# Sheet3.net
KiCad netlist of a schematic drawn in Altium Designer
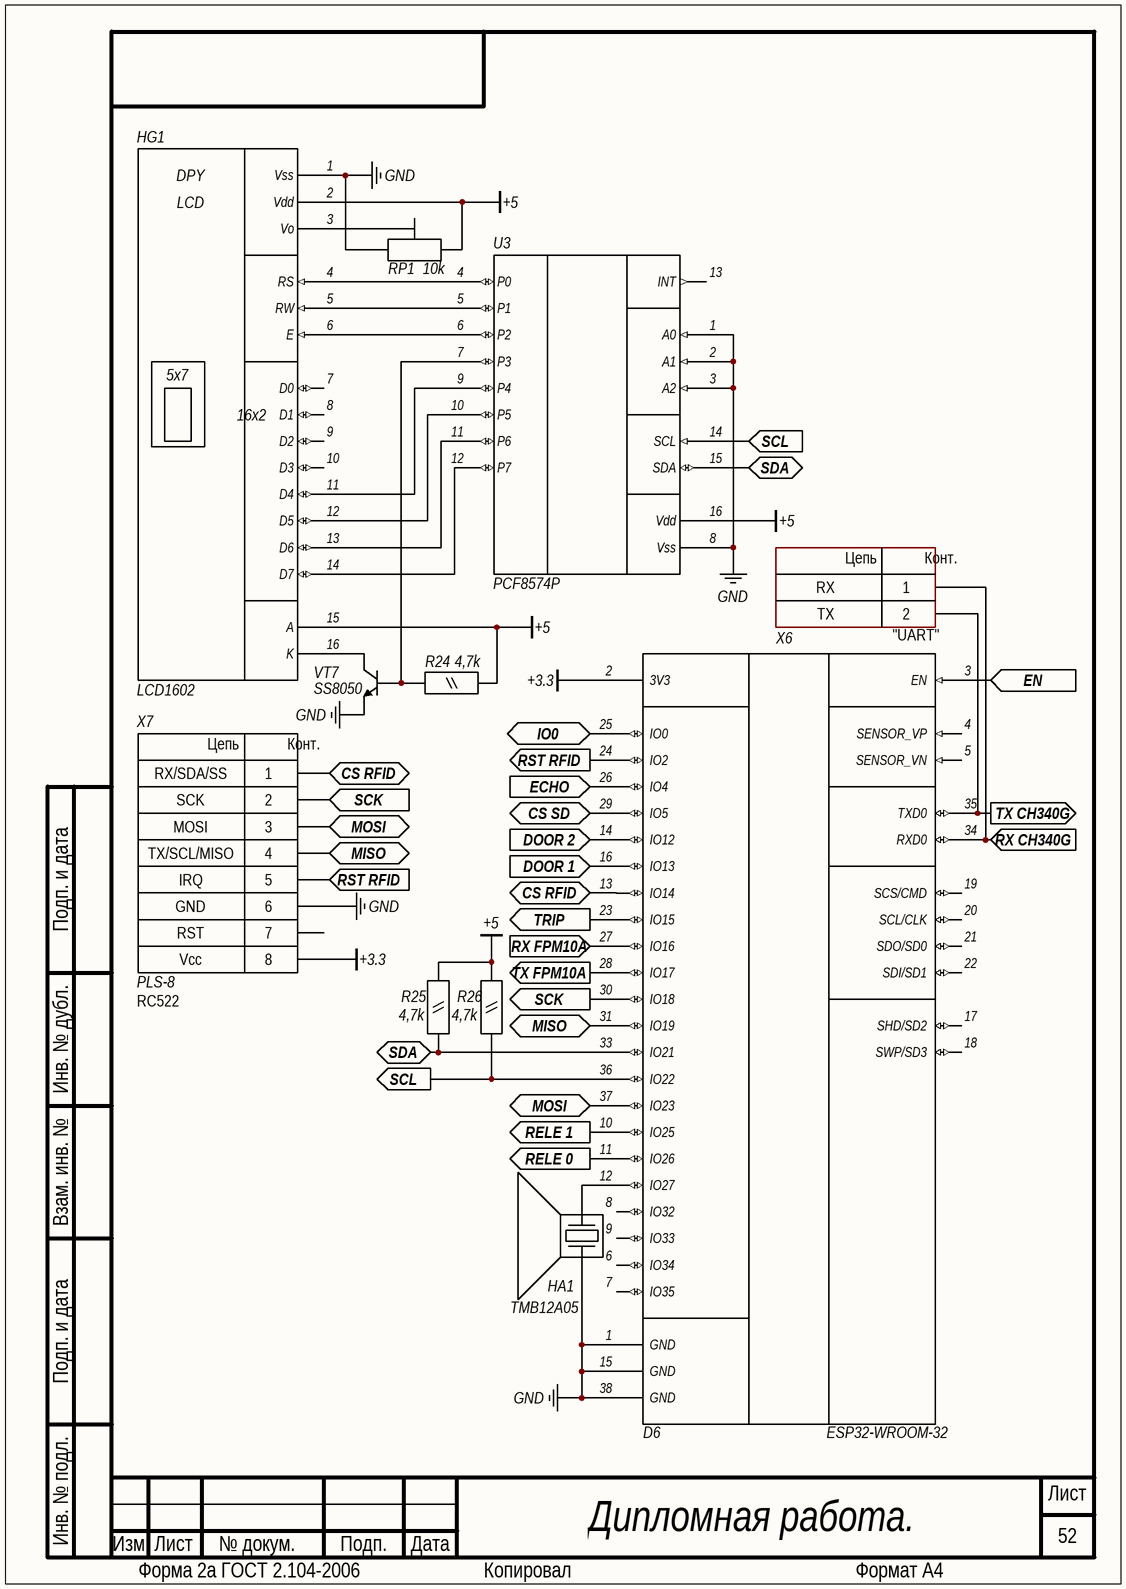
[diagram p0: Sheet3.SchDoc]

(export (version "E")
  (design (tool "Eeschema 10.0.6"))
  (components
    (comp (ref "D6")
      (value "ESP32-WROOM-32")
      (footprint "D ESP-WROOOM-32")
      (fields (field (name "MANUFACTURER") "Espressif Systems"))
      (libsource (lib "Schlib") (part "ESP32-WROOM"))
    )
    (comp (ref "HA1")
      (value "TMB12A05")
      (footprint "HA TMB12A05")
      (libsource (lib "Schlib") (part "Пьездодинамик"))
    )
    (comp (ref "HG1")
      (value "LCD1602")
      (footprint "X PBS-16")
      (description "Дисплей на основе контроллера HD44780.")
      (libsource (lib "Schlib") (part "LCD HD44780"))
    )
    (comp (ref "R24")
      (value "4,7k")
      (footprint "R SMD 0805")
      (description "R")
      (fields (field (name "POWER") "0.125"))
      (libsource (lib "") (part "Резистор 0.125 Вт_1"))
    )
    (comp (ref "R25")
      (value "4,7k")
      (footprint "R SMD 0805")
      (description "R")
      (fields (field (name "POWER") "0.125"))
      (libsource (lib "Schlib") (part "Резистор 0.125 Вт"))
    )
    (comp (ref "R26")
      (value "4,7k")
      (footprint "R SMD 0805")
      (description "R")
      (fields (field (name "POWER") "0.125"))
      (libsource (lib "Schlib") (part "Резистор 0.125 Вт"))
    )
    (comp (ref "RP1")
      (value "10k")
      (footprint "R ADJ-3296W")
      (libsource (lib "Schlib") (part "Подстроечный Резистор"))
    )
    (comp (ref "U3")
      (value "PCF8574P")
      (footprint "U DIP-16")
      (description "IIC расширитель.")
      (libsource (lib "Schlib") (part "PCF8574"))
    )
    (comp (ref "VT7")
      (value "SS8050")
      (footprint "U SOT-23-3")
      (fields (field (name "MANUFACTURER") "Hottech"))
      (libsource (lib "Schlib") (part "Биполярный Транзистор"))
    )
    (comp (ref "X6")
      (value "~")
      (footprint "CustomCase:CON: PLS-2")
      (fields
        (field (name "MANUFACTURER") "Connfly")
        (field (name "VALUEMANUFACTURERPARTNUMBER") "Connector, 2pin, 2.54mm, 500VAC, 3A")
        (field (name "PARTNUMBER") "PLS-2")
        (field (name "COMMENTTEXT") "\"UART\"")
        (field (name "TEXT1") "RX")
        (field (name "TEXT2") "TX")
      )
      (libsource (lib "Connector") (part "PLS-2"))
    )
    (comp (ref "X7")
      (value "PLS-8")
      (footprint "X PLS-8")
      (fields (field (name "COMMENTTEXT") "RC522"))
      (libsource (lib "Schlib") (part "PLS/PBS-8"))
    )
  )
  (nets
    (net (code "1") (name "+3.3") (class "Default")
      (node (ref "D6") (pin "2") (pinfunction "3V3_2") (pintype "power_in"))
      (node (ref "X7") (pin "8") (pinfunction "8_8") (pintype "power_in"))
    )
    (net (code "2") (name "+5") (class "Default")
      (node (ref "HG1") (pin "15") (pinfunction "A_15") (pintype "power_in"))
      (node (ref "HG1") (pin "2") (pinfunction "Vdd_2") (pintype "power_in"))
      (node (ref "R24") (pin "1") (pintype "passive"))
      (node (ref "R25") (pin "1") (pintype "passive"))
      (node (ref "R26") (pin "1") (pintype "passive"))
      (node (ref "RP1") (pin "1") (pintype "power_in"))
      (node (ref "U3") (pin "16") (pinfunction "Vdd_16") (pintype "power_in"))
    )
    (net (code "3") (name "/CS RFID") (class "Default")
      (node (ref "D6") (pin "13") (pinfunction "IO14_13") (pintype "bidirectional"))
      (node (ref "X7") (pin "1") (pinfunction "1_1") (pintype "passive"))
    )
    (net (code "4") (name "/CS SD") (class "Default")
      (node (ref "D6") (pin "29") (pinfunction "IO5_29") (pintype "bidirectional"))
    )
    (net (code "5") (name "/DOOR 1") (class "Default")
      (node (ref "D6") (pin "16") (pinfunction "IO13_16") (pintype "bidirectional"))
    )
    (net (code "6") (name "/DOOR 2") (class "Default")
      (node (ref "D6") (pin "14") (pinfunction "IO12_14") (pintype "bidirectional"))
    )
    (net (code "7") (name "/ECHO") (class "Default")
      (node (ref "D6") (pin "26") (pinfunction "IO4_26") (pintype "bidirectional"))
    )
    (net (code "8") (name "/EN") (class "Default")
      (node (ref "D6") (pin "3") (pinfunction "EN_3") (pintype "input"))
    )
    (net (code "9") (name "/IO0") (class "Default")
      (node (ref "D6") (pin "25") (pinfunction "IO0_25") (pintype "bidirectional"))
    )
    (net (code "10") (name "/MISO") (class "Default")
      (node (ref "D6") (pin "31") (pinfunction "IO19_31") (pintype "bidirectional"))
      (node (ref "X7") (pin "4") (pinfunction "4_4") (pintype "power_in"))
    )
    (net (code "11") (name "/MOSI") (class "Default")
      (node (ref "D6") (pin "37") (pinfunction "IO23_37") (pintype "bidirectional"))
      (node (ref "X7") (pin "3") (pinfunction "3_3") (pintype "power_in"))
    )
    (net (code "12") (name "/RELE 0") (class "Default")
      (node (ref "D6") (pin "11") (pinfunction "IO26_11") (pintype "bidirectional"))
    )
    (net (code "13") (name "/RELE 1") (class "Default")
      (node (ref "D6") (pin "10") (pinfunction "IO25_10") (pintype "bidirectional"))
    )
    (net (code "14") (name "/RST RFID") (class "Default")
      (node (ref "D6") (pin "24") (pinfunction "IO2_24") (pintype "bidirectional"))
      (node (ref "X7") (pin "5") (pinfunction "5_5") (pintype "power_in"))
    )
    (net (code "15") (name "/RX CH340G") (class "Default")
      (node (ref "D6") (pin "34") (pinfunction "RXD0_34") (pintype "bidirectional"))
      (node (ref "X6") (pin "1") (pinfunction "1_1") (pintype "passive"))
    )
    (net (code "16") (name "/RX FPM10A") (class "Default")
      (node (ref "D6") (pin "27") (pinfunction "IO16_27") (pintype "bidirectional"))
    )
    (net (code "17") (name "/SCK") (class "Default")
      (node (ref "D6") (pin "30") (pinfunction "IO18_30") (pintype "bidirectional"))
      (node (ref "X7") (pin "2") (pinfunction "2_2") (pintype "passive"))
    )
    (net (code "18") (name "/SCL") (class "Default")
      (node (ref "D6") (pin "36") (pinfunction "IO22_36") (pintype "bidirectional"))
      (node (ref "R26") (pin "2") (pintype "passive"))
      (node (ref "U3") (pin "14") (pinfunction "SCL_14") (pintype "input"))
    )
    (net (code "19") (name "/SDA") (class "Default")
      (node (ref "D6") (pin "33") (pinfunction "IO21_33") (pintype "bidirectional"))
      (node (ref "R25") (pin "2") (pintype "passive"))
      (node (ref "U3") (pin "15") (pinfunction "SDA_15") (pintype "bidirectional"))
    )
    (net (code "20") (name "/TRIP") (class "Default")
      (node (ref "D6") (pin "23") (pinfunction "IO15_23") (pintype "bidirectional"))
    )
    (net (code "21") (name "/TX CH340G") (class "Default")
      (node (ref "D6") (pin "35") (pinfunction "TXD0_35") (pintype "bidirectional"))
      (node (ref "X6") (pin "2") (pinfunction "2_2") (pintype "passive"))
    )
    (net (code "22") (name "/TX FPM10A") (class "Default")
      (node (ref "D6") (pin "28") (pinfunction "IO17_28") (pintype "bidirectional"))
    )
    (net (code "23") (name "GND") (class "Default")
      (node (ref "D6") (pin "1") (pinfunction "GND_1") (pintype "power_in"))
      (node (ref "D6") (pin "15") (pinfunction "GND_15") (pintype "power_in"))
      (node (ref "D6") (pin "38") (pinfunction "GND_38") (pintype "power_in"))
      (node (ref "HA1") (pin "2") (pinfunction "-_2") (pintype "passive"))
      (node (ref "HG1") (pin "1") (pinfunction "Vss_1") (pintype "power_in"))
      (node (ref "RP1") (pin "3") (pintype "power_in"))
      (node (ref "U3") (pin "1") (pinfunction "A0_1") (pintype "input"))
      (node (ref "U3") (pin "2") (pinfunction "A1_2") (pintype "input"))
      (node (ref "U3") (pin "3") (pinfunction "A2_3") (pintype "input"))
      (node (ref "U3") (pin "8") (pinfunction "Vss_8") (pintype "power_in"))
      (node (ref "VT7") (pin "1") (pinfunction "E_1") (pintype "open_emitter"))
      (node (ref "X7") (pin "6") (pinfunction "6_6") (pintype "power_in"))
    )
    (net (code "24") (name "Net-(D6-IO27)") (class "Default")
      (node (ref "D6") (pin "12") (pinfunction "IO27_12") (pintype "bidirectional"))
      (node (ref "HA1") (pin "1") (pinfunction "+_1") (pintype "passive"))
    )
    (net (code "25") (name "Net-(HG1-D4)") (class "Default")
      (node (ref "HG1") (pin "11") (pinfunction "D4_11") (pintype "bidirectional"))
      (node (ref "U3") (pin "9") (pinfunction "P4_9") (pintype "bidirectional"))
    )
    (net (code "26") (name "Net-(HG1-D5)") (class "Default")
      (node (ref "HG1") (pin "12") (pinfunction "D5_12") (pintype "bidirectional"))
      (node (ref "U3") (pin "10") (pinfunction "P5_10") (pintype "bidirectional"))
    )
    (net (code "27") (name "Net-(HG1-D6)") (class "Default")
      (node (ref "HG1") (pin "13") (pinfunction "D6_13") (pintype "bidirectional"))
      (node (ref "U3") (pin "11") (pinfunction "P6_11") (pintype "bidirectional"))
    )
    (net (code "28") (name "Net-(HG1-D7)") (class "Default")
      (node (ref "HG1") (pin "14") (pinfunction "D7_14") (pintype "bidirectional"))
      (node (ref "U3") (pin "12") (pinfunction "P7_12") (pintype "bidirectional"))
    )
    (net (code "29") (name "Net-(HG1-E)") (class "Default")
      (node (ref "HG1") (pin "6") (pinfunction "E_6") (pintype "input"))
      (node (ref "U3") (pin "6") (pinfunction "P2_6") (pintype "bidirectional"))
    )
    (net (code "30") (name "Net-(HG1-K)") (class "Default")
      (node (ref "HG1") (pin "16") (pinfunction "K_16") (pintype "power_in"))
      (node (ref "VT7") (pin "3") (pinfunction "C_3") (pintype "open_collector"))
    )
    (net (code "31") (name "Net-(HG1-RS)") (class "Default")
      (node (ref "HG1") (pin "4") (pinfunction "RS_4") (pintype "input"))
      (node (ref "U3") (pin "4") (pinfunction "P0_4") (pintype "bidirectional"))
    )
    (net (code "32") (name "Net-(HG1-RW)") (class "Default")
      (node (ref "HG1") (pin "5") (pinfunction "RW_5") (pintype "input"))
      (node (ref "U3") (pin "5") (pinfunction "P1_5") (pintype "bidirectional"))
    )
    (net (code "33") (name "Net-(HG1-Vo)") (class "Default")
      (node (ref "HG1") (pin "3") (pinfunction "Vo_3") (pintype "power_in"))
      (node (ref "RP1") (pin "2") (pintype "power_in"))
    )
    (net (code "34") (name "Net-(U3-P3)") (class "Default")
      (node (ref "R24") (pin "2") (pintype "passive"))
      (node (ref "U3") (pin "7") (pinfunction "P3_7") (pintype "bidirectional"))
      (node (ref "VT7") (pin "2") (pinfunction "B_2") (pintype "passive"))
    )
    (net (code "35") (name "unconnected-(D6-IO32-Pad8)") (class "Default")
      (node (ref "D6") (pin "8") (pinfunction "IO32_8") (pintype "bidirectional"))
    )
    (net (code "36") (name "unconnected-(D6-IO33-Pad9)") (class "Default")
      (node (ref "D6") (pin "9") (pinfunction "IO33_9") (pintype "bidirectional"))
    )
    (net (code "37") (name "unconnected-(D6-IO34-Pad6)") (class "Default")
      (node (ref "D6") (pin "6") (pinfunction "IO34_6") (pintype "bidirectional"))
    )
    (net (code "38") (name "unconnected-(D6-IO35-Pad7)") (class "Default")
      (node (ref "D6") (pin "7") (pinfunction "IO35_7") (pintype "bidirectional"))
    )
    (net (code "39") (name "unconnected-(D6-SCL{slash}CLK-Pad20)") (class "Default")
      (node (ref "D6") (pin "20") (pinfunction "SCL/CLK_20") (pintype "bidirectional"))
    )
    (net (code "40") (name "unconnected-(D6-SCS{slash}CMD-Pad19)") (class "Default")
      (node (ref "D6") (pin "19") (pinfunction "SCS/CMD_19") (pintype "bidirectional"))
    )
    (net (code "41") (name "unconnected-(D6-SDI{slash}SD1-Pad22)") (class "Default")
      (node (ref "D6") (pin "22") (pinfunction "SDI/SD1_22") (pintype "bidirectional"))
    )
    (net (code "42") (name "unconnected-(D6-SDO{slash}SD0-Pad21)") (class "Default")
      (node (ref "D6") (pin "21") (pinfunction "SDO/SD0_21") (pintype "bidirectional"))
    )
    (net (code "43") (name "unconnected-(D6-SENSOR_VN-Pad5)") (class "Default")
      (node (ref "D6") (pin "5") (pinfunction "SENSOR_VN_5") (pintype "input"))
    )
    (net (code "44") (name "unconnected-(D6-SENSOR_VP-Pad4)") (class "Default")
      (node (ref "D6") (pin "4") (pinfunction "SENSOR_VP_4") (pintype "input"))
    )
    (net (code "45") (name "unconnected-(D6-SHD{slash}SD2-Pad17)") (class "Default")
      (node (ref "D6") (pin "17") (pinfunction "SHD/SD2_17") (pintype "bidirectional"))
    )
    (net (code "46") (name "unconnected-(D6-SWP{slash}SD3-Pad18)") (class "Default")
      (node (ref "D6") (pin "18") (pinfunction "SWP/SD3_18") (pintype "bidirectional"))
    )
    (net (code "47") (name "unconnected-(HG1-D0-Pad7)") (class "Default")
      (node (ref "HG1") (pin "7") (pinfunction "D0_7") (pintype "bidirectional"))
    )
    (net (code "48") (name "unconnected-(HG1-D1-Pad8)") (class "Default")
      (node (ref "HG1") (pin "8") (pinfunction "D1_8") (pintype "bidirectional"))
    )
    (net (code "49") (name "unconnected-(HG1-D2-Pad9)") (class "Default")
      (node (ref "HG1") (pin "9") (pinfunction "D2_9") (pintype "bidirectional"))
    )
    (net (code "50") (name "unconnected-(HG1-D3-Pad10)") (class "Default")
      (node (ref "HG1") (pin "10") (pinfunction "D3_10") (pintype "bidirectional"))
    )
    (net (code "51") (name "unconnected-(U3-INT-Pad13)") (class "Default")
      (node (ref "U3") (pin "13") (pinfunction "INT_13") (pintype "output"))
    )
    (net (code "52") (name "unconnected-(X7-Pad7)") (class "Default")
      (node (ref "X7") (pin "7") (pinfunction "7_7") (pintype "power_in"))
    )
  )
)
